# Pi_MCU_shield.net
KiCad netlist of a schematic drawn in EAGLE
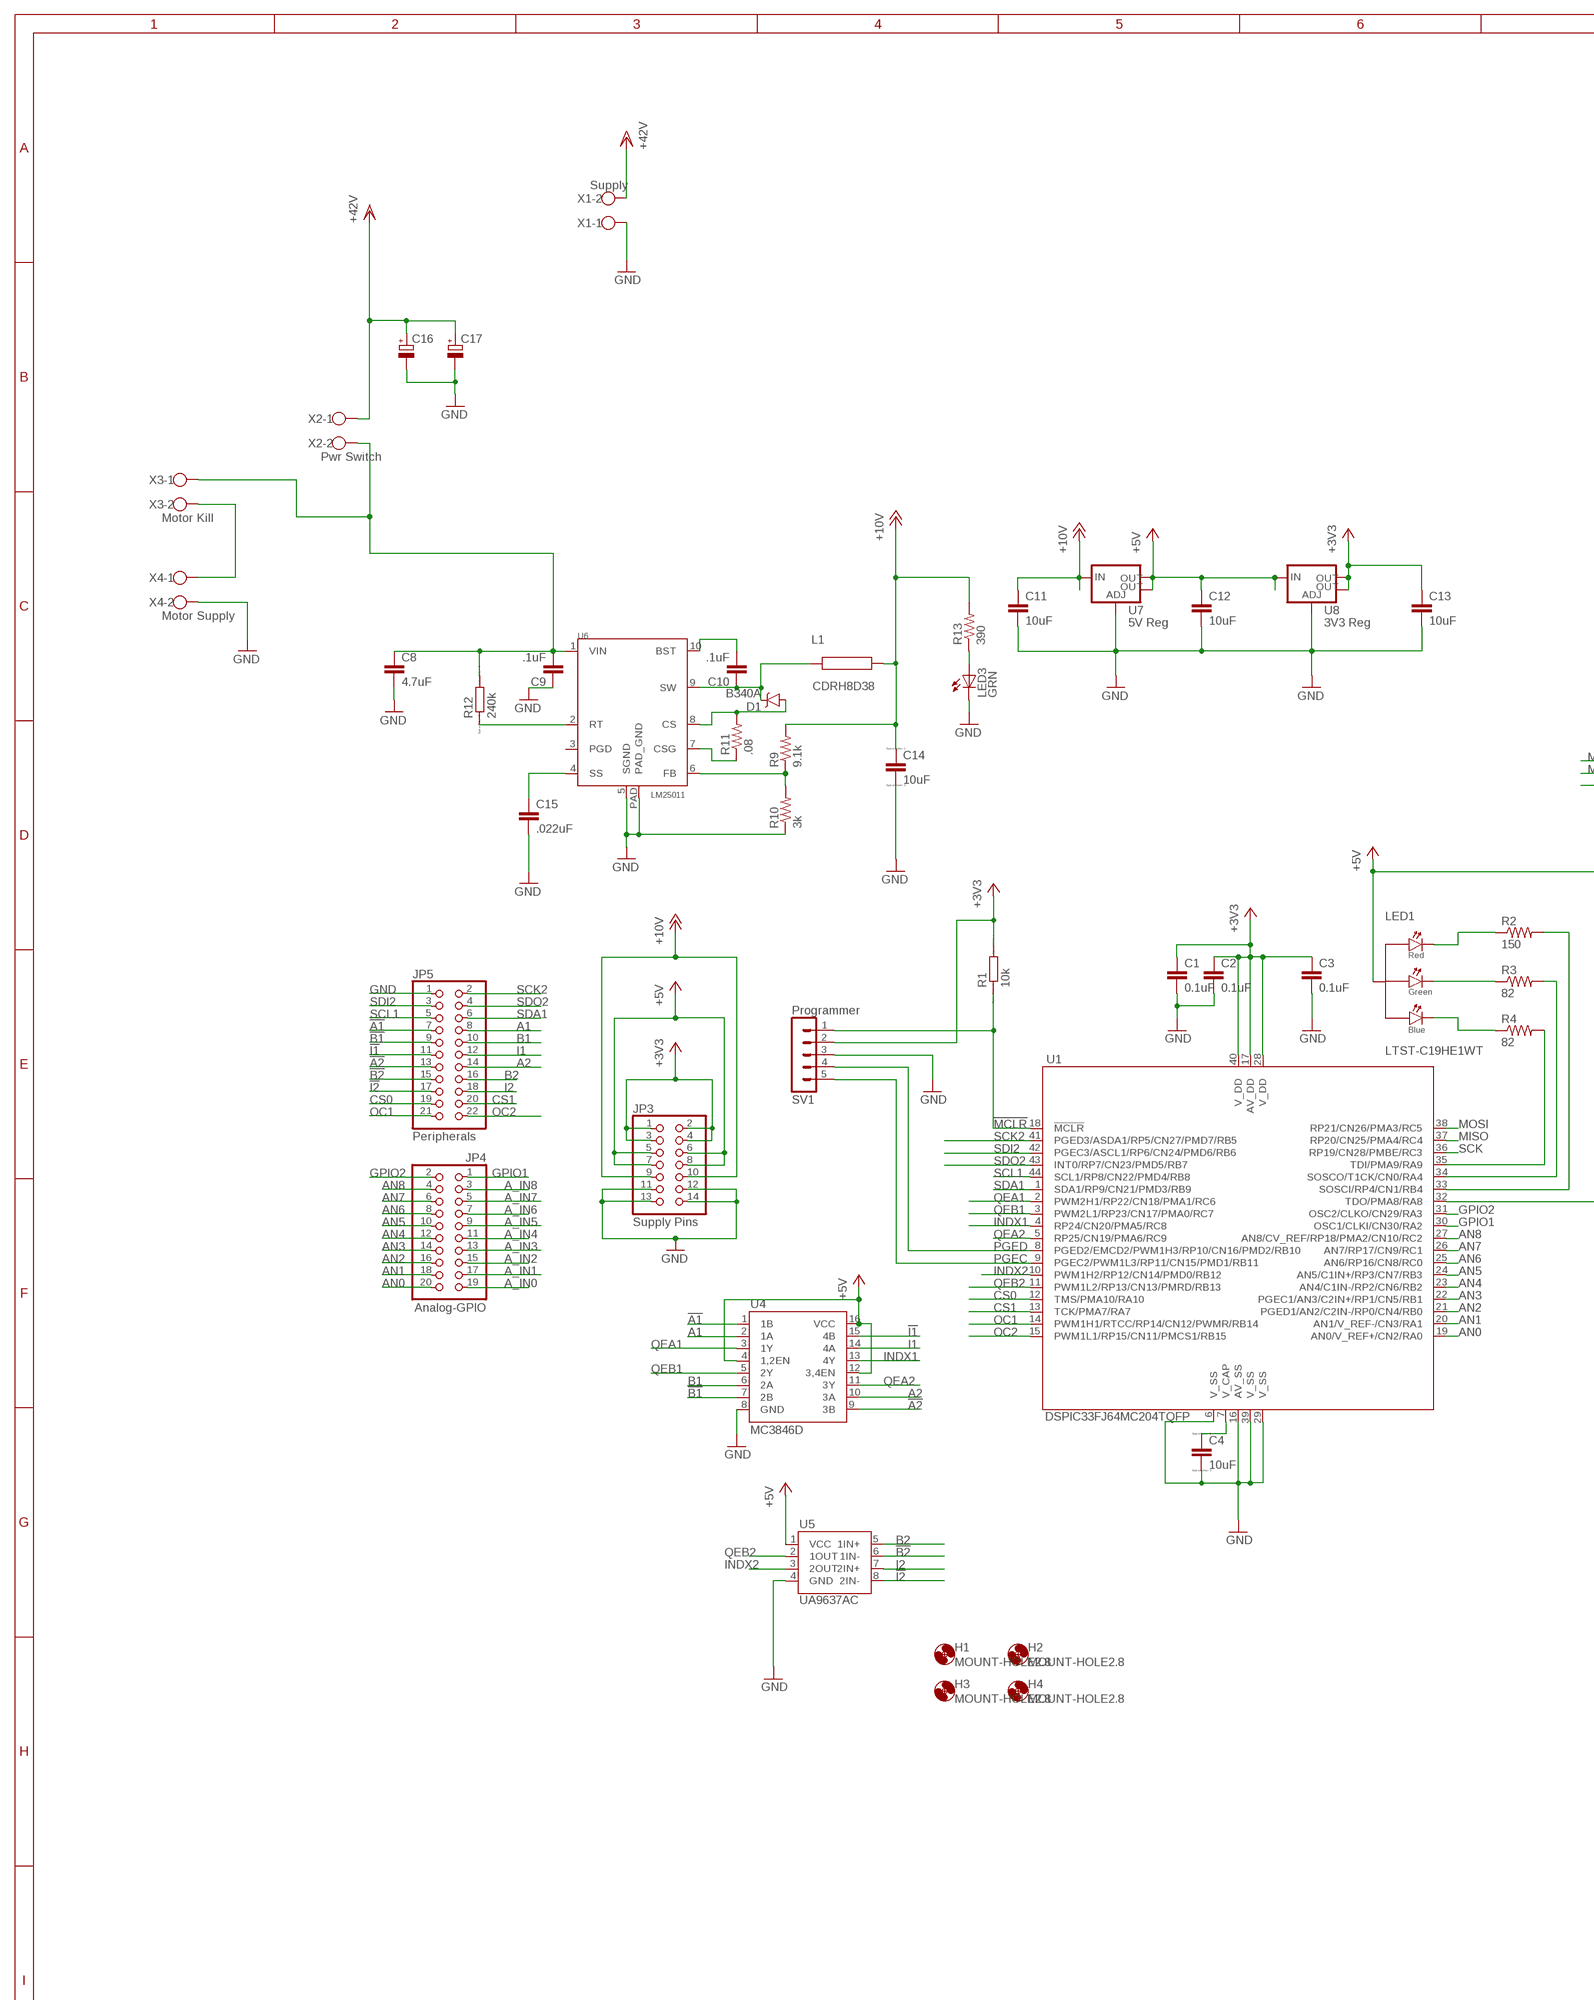
[diagram p0: schematic, sheet 1, part 1 of 2]
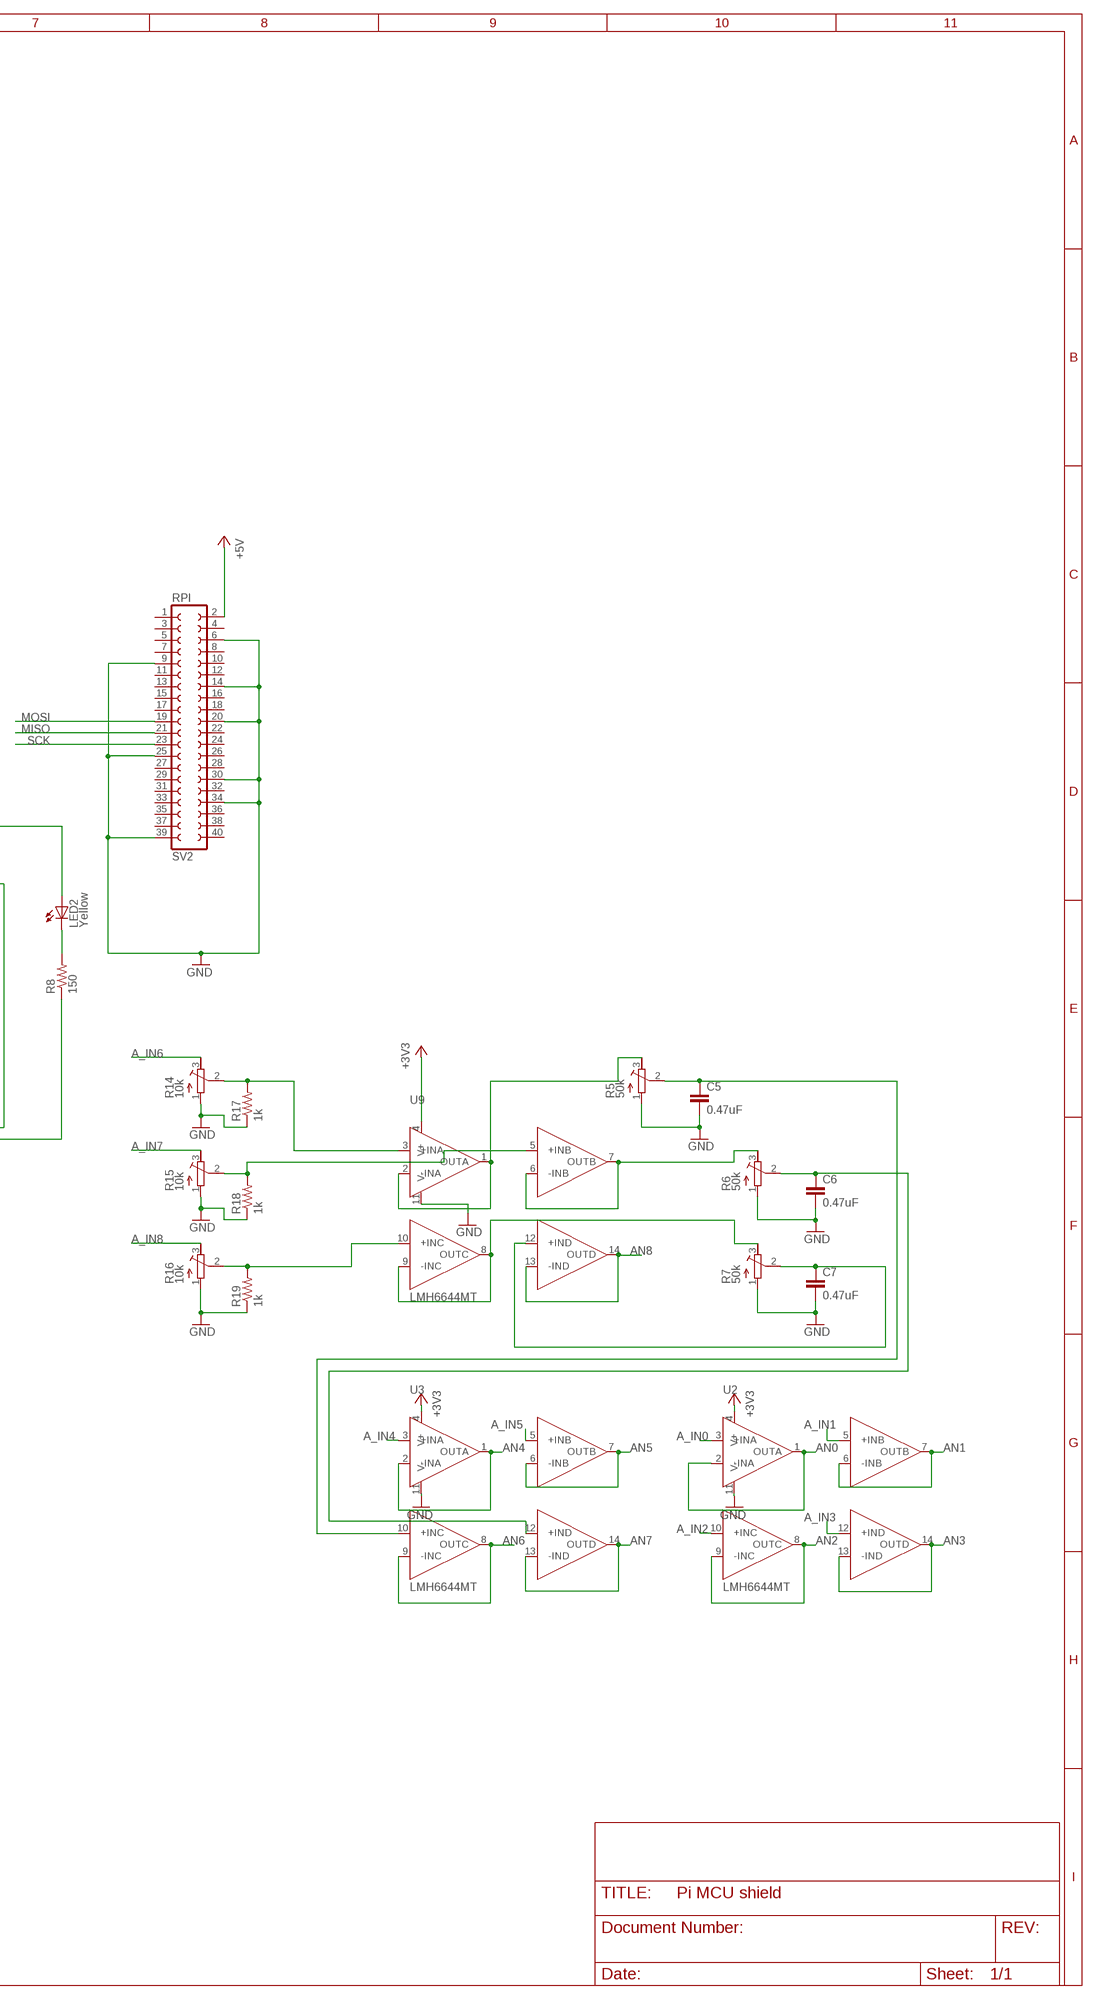
[diagram p1: schematic, sheet 1, part 2 of 2]

(export (version "E")
  (design (tool "Eeschema 10.0.6"))
  (components
    (comp (ref "C1")
      (value "0.1uF")
      (footprint "eagle-import:C0603")
      (libsource (lib "eagle-import") (part "C-EUC0603"))
    )
    (comp (ref "C2")
      (value "0.1uF")
      (footprint "eagle-import:C0603")
      (libsource (lib "eagle-import") (part "C-EUC0603"))
    )
    (comp (ref "C3")
      (value "0.1uF")
      (footprint "eagle-import:C0603")
      (libsource (lib "eagle-import") (part "C-EUC0603"))
    )
    (comp (ref "C4")
      (value "10uF")
      (footprint "eagle-import:C1206")
      (libsource (lib "eagle-import") (part "CC1206"))
    )
    (comp (ref "C5")
      (value "0.47uF")
      (footprint "eagle-import:C0603")
      (libsource (lib "eagle-import") (part "C-EUC0603"))
    )
    (comp (ref "C6")
      (value "0.47uF")
      (footprint "eagle-import:C0603")
      (libsource (lib "eagle-import") (part "C-EUC0603"))
    )
    (comp (ref "C7")
      (value "0.47uF")
      (footprint "eagle-import:C0603")
      (libsource (lib "eagle-import") (part "C-EUC0603"))
    )
    (comp (ref "C8")
      (value "4.7uF")
      (footprint "eagle-import:C1210")
      (libsource (lib "eagle-import") (part "C-EUC1210"))
    )
    (comp (ref "C9")
      (value ".1uF")
      (footprint "eagle-import:0603-CAP")
      (libsource (lib "eagle-import") (part "CAP0603-CAP"))
    )
    (comp (ref "C10")
      (value ".1uF")
      (footprint "eagle-import:0603-CAP")
      (libsource (lib "eagle-import") (part "CAP0603-CAP"))
    )
    (comp (ref "C11")
      (value "10uF")
      (footprint "eagle-import:C0805")
      (libsource (lib "eagle-import") (part "C-EUC0805"))
    )
    (comp (ref "C12")
      (value "10uF")
      (footprint "eagle-import:C0805")
      (libsource (lib "eagle-import") (part "C-EUC0805"))
    )
    (comp (ref "C13")
      (value "10uF")
      (footprint "eagle-import:C0805")
      (libsource (lib "eagle-import") (part "C-EUC0805"))
    )
    (comp (ref "C14")
      (value "10uF")
      (footprint "eagle-import:C1206")
      (libsource (lib "eagle-import") (part "CC1206"))
    )
    (comp (ref "C15")
      (value ".022uF")
      (footprint "eagle-import:0603-CAP")
      (libsource (lib "eagle-import") (part "CAP0603-CAP"))
    )
    (comp (ref "C16")
      (value "CPOL-EUE5-13")
      (footprint "eagle-import:E5-13")
      (libsource (lib "eagle-import") (part "CPOL-EUE5-13"))
    )
    (comp (ref "C17")
      (value "CPOL-EUE5-13")
      (footprint "eagle-import:E5-13")
      (libsource (lib "eagle-import") (part "CPOL-EUE5-13"))
    )
    (comp (ref "D1")
      (value "B340A")
      (footprint "eagle-import:SMA-DIODE")
      (libsource (lib "eagle-import") (part "DIODE-SCHOTTKY-B340A"))
    )
    (comp (ref "H1")
      (value "MOUNT-HOLE2.8")
      (footprint "eagle-import:2,8")
      (libsource (lib "eagle-import") (part "MOUNT-HOLE2.8"))
    )
    (comp (ref "H2")
      (value "MOUNT-HOLE2.8")
      (footprint "eagle-import:2,8")
      (libsource (lib "eagle-import") (part "MOUNT-HOLE2.8"))
    )
    (comp (ref "H3")
      (value "MOUNT-HOLE2.8")
      (footprint "eagle-import:2,8")
      (libsource (lib "eagle-import") (part "MOUNT-HOLE2.8"))
    )
    (comp (ref "H4")
      (value "MOUNT-HOLE2.8")
      (footprint "eagle-import:2,8")
      (libsource (lib "eagle-import") (part "MOUNT-HOLE2.8"))
    )
    (comp (ref "JP3")
      (value "Supply Pins")
      (footprint "eagle-import:2X07")
      (libsource (lib "eagle-import") (part "PINHD-2X7"))
    )
    (comp (ref "JP4")
      (value "Analog-GPIO")
      (footprint "eagle-import:2X10")
      (libsource (lib "eagle-import") (part "PINHD-2X10"))
    )
    (comp (ref "JP5")
      (value "Peripherals")
      (footprint "eagle-import:2X11")
      (libsource (lib "eagle-import") (part "PINHD-2X11"))
    )
    (comp (ref "L1")
      (value "CDRH8D38")
      (footprint "eagle-import:CDRH8D38")
      (libsource (lib "eagle-import") (part "CDRH8D38"))
    )
    (comp (ref "LED1")
      (value "LTST-C19HE1WT")
      (footprint "eagle-import:0606")
      (libsource (lib "eagle-import") (part "LTST-C19HE1WT"))
    )
    (comp (ref "LED2")
      (value "Yellow")
      (footprint "eagle-import:SML0603")
      (libsource (lib "eagle-import") (part "LEDSML0603"))
    )
    (comp (ref "LED3")
      (value "GRN")
      (footprint "eagle-import:CHIP-LED0805")
      (libsource (lib "eagle-import") (part "LEDCHIP-LED0805"))
    )
    (comp (ref "R1")
      (value "10k")
      (footprint "eagle-import:R0805")
      (libsource (lib "eagle-import") (part "R"))
    )
    (comp (ref "R2")
      (value "150")
      (footprint "eagle-import:R0603")
      (libsource (lib "eagle-import") (part "R-US_R0603"))
    )
    (comp (ref "R3")
      (value "82")
      (footprint "eagle-import:R0603")
      (libsource (lib "eagle-import") (part "R-US_R0603"))
    )
    (comp (ref "R4")
      (value "82")
      (footprint "eagle-import:R0603")
      (libsource (lib "eagle-import") (part "R-US_R0603"))
    )
    (comp (ref "R5")
      (value "50k")
      (footprint "eagle-import:RTRIM3224J")
      (libsource (lib "eagle-import") (part "R-TRIMM3224J"))
    )
    (comp (ref "R6")
      (value "50k")
      (footprint "eagle-import:RTRIM3224J")
      (libsource (lib "eagle-import") (part "R-TRIMM3224J"))
    )
    (comp (ref "R7")
      (value "50k")
      (footprint "eagle-import:RTRIM3224J")
      (libsource (lib "eagle-import") (part "R-TRIMM3224J"))
    )
    (comp (ref "R8")
      (value "150")
      (footprint "eagle-import:R0603")
      (libsource (lib "eagle-import") (part "R-US_R0603"))
    )
    (comp (ref "R9")
      (value "9.1k")
      (footprint "eagle-import:0603-RES")
      (libsource (lib "eagle-import") (part "RESISTOR0603-RES"))
    )
    (comp (ref "R10")
      (value "3k")
      (footprint "eagle-import:0603-RES")
      (libsource (lib "eagle-import") (part "RESISTOR0603-RES"))
    )
    (comp (ref "R11")
      (value ".08")
      (footprint "eagle-import:0603-RES")
      (libsource (lib "eagle-import") (part "RESISTOR0603-RES"))
    )
    (comp (ref "R12")
      (value "240k")
      (footprint "eagle-import:R0805")
      (libsource (lib "eagle-import") (part "R"))
    )
    (comp (ref "R13")
      (value "390")
      (footprint "eagle-import:0603-RES")
      (libsource (lib "eagle-import") (part "RESISTOR0603-RES"))
    )
    (comp (ref "R14")
      (value "10k")
      (footprint "eagle-import:RTRIM3224J")
      (libsource (lib "eagle-import") (part "R-TRIMM3224J"))
    )
    (comp (ref "R15")
      (value "10k")
      (footprint "eagle-import:RTRIM3224J")
      (libsource (lib "eagle-import") (part "R-TRIMM3224J"))
    )
    (comp (ref "R16")
      (value "10k")
      (footprint "eagle-import:RTRIM3224J")
      (libsource (lib "eagle-import") (part "R-TRIMM3224J"))
    )
    (comp (ref "R17")
      (value "1k")
      (footprint "eagle-import:R0603")
      (libsource (lib "eagle-import") (part "R-US_R0603"))
    )
    (comp (ref "R18")
      (value "1k")
      (footprint "eagle-import:R0603")
      (libsource (lib "eagle-import") (part "R-US_R0603"))
    )
    (comp (ref "R19")
      (value "1k")
      (footprint "eagle-import:R0603")
      (libsource (lib "eagle-import") (part "R-US_R0603"))
    )
    (comp (ref "SV1")
      (value "Programmer")
      (footprint "eagle-import:MA05-1")
      (libsource (lib "eagle-import") (part "MA05-1"))
    )
    (comp (ref "SV2")
      (value "RPI")
      (footprint "eagle-import:FE20-2")
      (libsource (lib "eagle-import") (part "FE20-2"))
    )
    (comp (ref "U1")
      (value "DSPIC33FJ64MC204TQFP")
      (footprint "eagle-import:TQFP44")
      (libsource (lib "eagle-import") (part "DSPIC33FJ64MC204TQFP"))
    )
    (comp (ref "U2")
      (value "LMH6644MT")
      (footprint "eagle-import:TSSOP14")
      (libsource (lib "eagle-import") (part "LMH6644MT"))
    )
    (comp (ref "U3")
      (value "LMH6644MT")
      (footprint "eagle-import:TSSOP14")
      (libsource (lib "eagle-import") (part "LMH6644MT"))
    )
    (comp (ref "U4")
      (value "MC3846D")
      (footprint "eagle-import:SO-16")
      (libsource (lib "eagle-import") (part "MC3846D"))
    )
    (comp (ref "U5")
      (value "UA9637AC")
      (footprint "eagle-import:SO-08")
      (libsource (lib "eagle-import") (part "UA9637AC"))
    )
    (comp (ref "U6")
      (value "LM25011")
      (footprint "eagle-import:HVSS0P-10")
      (libsource (lib "eagle-import") (part "LM25011"))
    )
    (comp (ref "U7")
      (value "5V Reg")
      (footprint "eagle-import:SOT223")
      (libsource (lib "eagle-import") (part "V_REG_LM1117SOT223"))
    )
    (comp (ref "U8")
      (value "3V3 Reg")
      (footprint "eagle-import:SOT223")
      (libsource (lib "eagle-import") (part "V_REG_LM1117SOT223"))
    )
    (comp (ref "U9")
      (value "LMH6644MT")
      (footprint "eagle-import:TSSOP14")
      (libsource (lib "eagle-import") (part "LMH6644MT"))
    )
    (comp (ref "X1")
      (value "Supply")
      (footprint "eagle-import:W237-102")
      (fields (field (name "MPN") "237-102"))
      (libsource (lib "eagle-import") (part "W237-102"))
    )
    (comp (ref "X2")
      (value "Pwr Switch")
      (footprint "eagle-import:W237-102")
      (fields (field (name "MPN") "237-102"))
      (libsource (lib "eagle-import") (part "W237-102"))
    )
    (comp (ref "X3")
      (value "Motor Kill")
      (footprint "eagle-import:W237-102")
      (fields (field (name "MPN") "237-102"))
      (libsource (lib "eagle-import") (part "W237-102"))
    )
    (comp (ref "X4")
      (value "Motor Supply")
      (footprint "eagle-import:W237-102")
      (fields (field (name "MPN") "237-102"))
      (libsource (lib "eagle-import") (part "W237-102"))
    )
  )
  (nets
    (net (code "1") (name "+3V3") (class "Default")
      (node (ref "C1") (pin "1") (pinfunction "1_1") (pintype "passive"))
      (node (ref "C13") (pin "1") (pinfunction "1_1") (pintype "passive"))
      (node (ref "C2") (pin "1") (pinfunction "1_1") (pintype "passive"))
      (node (ref "C3") (pin "1") (pinfunction "1_1") (pintype "passive"))
      (node (ref "JP3") (pin "1") (pinfunction "1_1") (pintype "passive"))
      (node (ref "JP3") (pin "2") (pinfunction "2_2") (pintype "passive"))
      (node (ref "JP3") (pin "3") (pinfunction "3_3") (pintype "passive"))
      (node (ref "JP3") (pin "4") (pinfunction "4_4") (pintype "passive"))
      (node (ref "R1") (pin "2") (pinfunction "2_2") (pintype "passive"))
      (node (ref "SV1") (pin "2") (pinfunction "2_2") (pintype "passive"))
      (node (ref "U1") (pin "17") (pinfunction "AV_DD_17") (pintype "power_in"))
      (node (ref "U1") (pin "28") (pinfunction "V_DD_28") (pintype "power_in"))
      (node (ref "U1") (pin "40") (pinfunction "V_DD_40") (pintype "power_in"))
      (node (ref "U2") (pin "4") (pinfunction "V+_4") (pintype "bidirectional"))
      (node (ref "U3") (pin "4") (pinfunction "V+_4") (pintype "bidirectional"))
      (node (ref "U8") (pin "2") (pinfunction "OUT_2") (pintype "output"))
      (node (ref "U8") (pin "4") (pinfunction "OUT_4") (pintype "output"))
      (node (ref "U9") (pin "4") (pinfunction "V+_4") (pintype "bidirectional"))
    )
    (net (code "2") (name "+5V") (class "Default")
      (node (ref "C12") (pin "1") (pinfunction "1_1") (pintype "passive"))
      (node (ref "JP3") (pin "5") (pinfunction "5_5") (pintype "passive"))
      (node (ref "JP3") (pin "6") (pinfunction "6_6") (pintype "passive"))
      (node (ref "JP3") (pin "7") (pinfunction "7_7") (pintype "passive"))
      (node (ref "JP3") (pin "8") (pinfunction "8_8") (pintype "passive"))
      (node (ref "LED1") (pin "4") (pinfunction "ANODE_4") (pintype "passive"))
      (node (ref "LED2") (pin "A") (pinfunction "A_A") (pintype "passive"))
      (node (ref "SV2") (pin "2") (pinfunction "2_2") (pintype "passive"))
      (node (ref "U4") (pin "12") (pinfunction "3,4EN_12") (pintype "bidirectional"))
      (node (ref "U4") (pin "16") (pinfunction "VCC_16") (pintype "power_in"))
      (node (ref "U4") (pin "4") (pinfunction "1,2EN_4") (pintype "input"))
      (node (ref "U5") (pin "1") (pinfunction "VCC_1") (pintype "power_in"))
      (node (ref "U7") (pin "2") (pinfunction "OUT_2") (pintype "output"))
      (node (ref "U7") (pin "4") (pinfunction "OUT_4") (pintype "output"))
      (node (ref "U8") (pin "3") (pinfunction "IN_3") (pintype "input"))
    )
    (net (code "3") (name "+10V") (class "Default")
      (node (ref "C11") (pin "1") (pinfunction "1_1") (pintype "passive"))
      (node (ref "C14") (pin "1") (pinfunction "1_1") (pintype "passive"))
      (node (ref "JP3") (pin "10") (pinfunction "10_10") (pintype "passive"))
      (node (ref "JP3") (pin "9") (pinfunction "9_9") (pintype "passive"))
      (node (ref "L1") (pin "P$2") (pinfunction "2_P$2") (pintype "passive"))
      (node (ref "R13") (pin "2") (pinfunction "2_2") (pintype "passive"))
      (node (ref "R9") (pin "2") (pinfunction "2_2") (pintype "passive"))
      (node (ref "U7") (pin "3") (pinfunction "IN_3") (pintype "input"))
    )
    (net (code "4") (name "+42V") (class "Default")
      (node (ref "C16") (pin "+") (pinfunction "+_+") (pintype "passive"))
      (node (ref "C17") (pin "+") (pinfunction "+_+") (pintype "passive"))
      (node (ref "X1") (pin "2") (pinfunction "KL_2") (pintype "passive"))
      (node (ref "X2") (pin "1") (pinfunction "KL_1") (pintype "passive"))
    )
    (net (code "5") (name "/A1") (class "Default")
      (node (ref "JP5") (pin "8") (pinfunction "8_8") (pintype "passive"))
      (node (ref "U4") (pin "2") (pinfunction "1A_2") (pintype "input"))
    )
    (net (code "6") (name "/A2") (class "Default")
      (node (ref "JP5") (pin "14") (pinfunction "14_14") (pintype "passive"))
      (node (ref "U4") (pin "10") (pinfunction "3A_10") (pintype "input"))
    )
    (net (code "7") (name "/AN0") (class "Default")
      (node (ref "JP4") (pin "20") (pinfunction "20_20") (pintype "passive"))
      (node (ref "U1") (pin "19") (pinfunction "AN0/V_REF+/CN2/RA0_19") (pintype "bidirectional"))
      (node (ref "U2") (pin "1") (pinfunction "OUTA_1") (pintype "bidirectional"))
      (node (ref "U2") (pin "2") (pinfunction "-INA_2") (pintype "bidirectional"))
    )
    (net (code "8") (name "/AN1") (class "Default")
      (node (ref "JP4") (pin "18") (pinfunction "18_18") (pintype "passive"))
      (node (ref "U1") (pin "20") (pinfunction "AN1/V_REF-/CN3/RA1_20") (pintype "bidirectional"))
      (node (ref "U2") (pin "6") (pinfunction "-INB_6") (pintype "bidirectional"))
      (node (ref "U2") (pin "7") (pinfunction "OUTB_7") (pintype "bidirectional"))
    )
    (net (code "9") (name "/AN2") (class "Default")
      (node (ref "JP4") (pin "16") (pinfunction "16_16") (pintype "passive"))
      (node (ref "U1") (pin "21") (pinfunction "PGED1/AN2/C2IN-/RP0/CN4/RB0_21") (pintype "bidirectional"))
      (node (ref "U2") (pin "8") (pinfunction "OUTC_8") (pintype "bidirectional"))
      (node (ref "U2") (pin "9") (pinfunction "-INC_9") (pintype "bidirectional"))
    )
    (net (code "10") (name "/AN3") (class "Default")
      (node (ref "JP4") (pin "14") (pinfunction "14_14") (pintype "passive"))
      (node (ref "U1") (pin "22") (pinfunction "PGEC1/AN3/C2IN+/RP1/CN5/RB1_22") (pintype "bidirectional"))
      (node (ref "U2") (pin "13") (pinfunction "-IND_13") (pintype "bidirectional"))
      (node (ref "U2") (pin "14") (pinfunction "OUTD_14") (pintype "bidirectional"))
    )
    (net (code "11") (name "/AN4") (class "Default")
      (node (ref "JP4") (pin "12") (pinfunction "12_12") (pintype "passive"))
      (node (ref "U1") (pin "23") (pinfunction "AN4/C1IN-/RP2/CN6/RB2_23") (pintype "bidirectional"))
      (node (ref "U3") (pin "1") (pinfunction "OUTA_1") (pintype "bidirectional"))
      (node (ref "U3") (pin "2") (pinfunction "-INA_2") (pintype "bidirectional"))
    )
    (net (code "12") (name "/AN5") (class "Default")
      (node (ref "JP4") (pin "10") (pinfunction "10_10") (pintype "passive"))
      (node (ref "U1") (pin "24") (pinfunction "AN5/C1IN+/RP3/CN7/RB3_24") (pintype "bidirectional"))
      (node (ref "U3") (pin "6") (pinfunction "-INB_6") (pintype "bidirectional"))
      (node (ref "U3") (pin "7") (pinfunction "OUTB_7") (pintype "bidirectional"))
    )
    (net (code "13") (name "/AN6") (class "Default")
      (node (ref "JP4") (pin "8") (pinfunction "8_8") (pintype "passive"))
      (node (ref "U1") (pin "25") (pinfunction "AN6/RP16/CN8/RC0_25") (pintype "bidirectional"))
      (node (ref "U3") (pin "8") (pinfunction "OUTC_8") (pintype "bidirectional"))
      (node (ref "U3") (pin "9") (pinfunction "-INC_9") (pintype "bidirectional"))
    )
    (net (code "14") (name "/AN7") (class "Default")
      (node (ref "JP4") (pin "6") (pinfunction "6_6") (pintype "passive"))
      (node (ref "U1") (pin "26") (pinfunction "AN7/RP17/CN9/RC1_26") (pintype "bidirectional"))
      (node (ref "U3") (pin "13") (pinfunction "-IND_13") (pintype "bidirectional"))
      (node (ref "U3") (pin "14") (pinfunction "OUTD_14") (pintype "bidirectional"))
    )
    (net (code "15") (name "/AN8") (class "Default")
      (node (ref "JP4") (pin "4") (pinfunction "4_4") (pintype "passive"))
      (node (ref "U1") (pin "27") (pinfunction "AN8/CV_REF/RP18/PMA2/CN10/RC2_27") (pintype "bidirectional"))
      (node (ref "U9") (pin "13") (pinfunction "-IND_13") (pintype "bidirectional"))
      (node (ref "U9") (pin "14") (pinfunction "OUTD_14") (pintype "bidirectional"))
    )
    (net (code "16") (name "/A_IN0") (class "Default")
      (node (ref "JP4") (pin "19") (pinfunction "19_19") (pintype "passive"))
      (node (ref "U2") (pin "3") (pinfunction "+INA_3") (pintype "bidirectional"))
    )
    (net (code "17") (name "/A_IN1") (class "Default")
      (node (ref "JP4") (pin "17") (pinfunction "17_17") (pintype "passive"))
      (node (ref "U2") (pin "5") (pinfunction "+INB_5") (pintype "bidirectional"))
    )
    (net (code "18") (name "/A_IN2") (class "Default")
      (node (ref "JP4") (pin "15") (pinfunction "15_15") (pintype "passive"))
      (node (ref "U2") (pin "10") (pinfunction "+INC_10") (pintype "bidirectional"))
    )
    (net (code "19") (name "/A_IN3") (class "Default")
      (node (ref "JP4") (pin "13") (pinfunction "13_13") (pintype "passive"))
      (node (ref "U2") (pin "12") (pinfunction "+IND_12") (pintype "bidirectional"))
    )
    (net (code "20") (name "/A_IN4") (class "Default")
      (node (ref "JP4") (pin "11") (pinfunction "11_11") (pintype "passive"))
      (node (ref "U3") (pin "3") (pinfunction "+INA_3") (pintype "bidirectional"))
    )
    (net (code "21") (name "/A_IN5") (class "Default")
      (node (ref "JP4") (pin "9") (pinfunction "9_9") (pintype "passive"))
      (node (ref "U3") (pin "5") (pinfunction "+INB_5") (pintype "bidirectional"))
    )
    (net (code "22") (name "/A_IN6") (class "Default")
      (node (ref "JP4") (pin "7") (pinfunction "7_7") (pintype "passive"))
      (node (ref "R14") (pin "3") (pinfunction "E_3") (pintype "passive"))
    )
    (net (code "23") (name "/A_IN7") (class "Default")
      (node (ref "JP4") (pin "5") (pinfunction "5_5") (pintype "passive"))
      (node (ref "R15") (pin "3") (pinfunction "E_3") (pintype "passive"))
    )
    (net (code "24") (name "/A_IN8") (class "Default")
      (node (ref "JP4") (pin "3") (pinfunction "3_3") (pintype "passive"))
      (node (ref "R16") (pin "3") (pinfunction "E_3") (pintype "passive"))
    )
    (net (code "25") (name "/B1") (class "Default")
      (node (ref "JP5") (pin "10") (pinfunction "10_10") (pintype "passive"))
      (node (ref "U4") (pin "6") (pinfunction "2A_6") (pintype "input"))
    )
    (net (code "26") (name "/B2") (class "Default")
      (node (ref "JP5") (pin "16") (pinfunction "16_16") (pintype "passive"))
      (node (ref "U5") (pin "5") (pinfunction "1IN+_5") (pintype "input"))
    )
    (net (code "27") (name "/CS0") (class "Default")
      (node (ref "JP5") (pin "19") (pinfunction "19_19") (pintype "passive"))
      (node (ref "U1") (pin "12") (pinfunction "TMS/PMA10/RA10_12") (pintype "bidirectional"))
    )
    (net (code "28") (name "/CS1") (class "Default")
      (node (ref "JP5") (pin "20") (pinfunction "20_20") (pintype "passive"))
      (node (ref "U1") (pin "13") (pinfunction "TCK/PMA7/RA7_13") (pintype "bidirectional"))
    )
    (net (code "29") (name "/GPIO1") (class "Default")
      (node (ref "JP4") (pin "1") (pinfunction "1_1") (pintype "passive"))
      (node (ref "U1") (pin "30") (pinfunction "OSC1/CLKI/CN30/RA2_30") (pintype "bidirectional"))
    )
    (net (code "30") (name "/GPIO2") (class "Default")
      (node (ref "JP4") (pin "2") (pinfunction "2_2") (pintype "passive"))
      (node (ref "U1") (pin "31") (pinfunction "OSC2/CLKO/CN29/RA3_31") (pintype "bidirectional"))
    )
    (net (code "31") (name "/I1") (class "Default")
      (node (ref "JP5") (pin "12") (pinfunction "12_12") (pintype "passive"))
      (node (ref "U4") (pin "14") (pinfunction "4A_14") (pintype "input"))
    )
    (net (code "32") (name "/I2") (class "Default")
      (node (ref "JP5") (pin "18") (pinfunction "18_18") (pintype "passive"))
      (node (ref "U5") (pin "7") (pinfunction "2IN+_7") (pintype "input"))
    )
    (net (code "33") (name "/INDX1") (class "Default")
      (node (ref "U1") (pin "4") (pinfunction "RP24/CN20/PMA5/RC8_4") (pintype "bidirectional"))
      (node (ref "U4") (pin "13") (pinfunction "4Y_13") (pintype "output"))
    )
    (net (code "34") (name "/INDX2") (class "Default")
      (node (ref "U1") (pin "10") (pinfunction "PWM1H2/RP12/CN14/PMD0/RB12_10") (pintype "bidirectional"))
      (node (ref "U5") (pin "3") (pinfunction "2OUT_3") (pintype "output"))
    )
    (net (code "35") (name "/MISO") (class "Default")
      (node (ref "SV2") (pin "21") (pinfunction "21_21") (pintype "passive"))
      (node (ref "U1") (pin "37") (pinfunction "RP20/CN25/PMA4/RC4_37") (pintype "bidirectional"))
    )
    (net (code "36") (name "/MOSI") (class "Default")
      (node (ref "SV2") (pin "19") (pinfunction "19_19") (pintype "passive"))
      (node (ref "U1") (pin "38") (pinfunction "RP21/CN26/PMA3/RC5_38") (pintype "bidirectional"))
    )
    (net (code "37") (name "/OC1") (class "Default")
      (node (ref "JP5") (pin "21") (pinfunction "21_21") (pintype "passive"))
      (node (ref "U1") (pin "14") (pinfunction "PWM1H1/RTCC/RP14/CN12/PWMR/RB14_14") (pintype "bidirectional"))
    )
    (net (code "38") (name "/OC2") (class "Default")
      (node (ref "JP5") (pin "22") (pinfunction "22_22") (pintype "passive"))
      (node (ref "U1") (pin "15") (pinfunction "PWM1L1/RP15/CN11/PMCS1/RB15_15") (pintype "bidirectional"))
    )
    (net (code "39") (name "/PGEC") (class "Default")
      (node (ref "SV1") (pin "5") (pinfunction "5_5") (pintype "passive"))
      (node (ref "U1") (pin "9") (pinfunction "PGEC2/PWM1L3/RP11/CN15/PMD1/RB11_9") (pintype "bidirectional"))
    )
    (net (code "40") (name "/PGED") (class "Default")
      (node (ref "SV1") (pin "4") (pinfunction "4_4") (pintype "passive"))
      (node (ref "U1") (pin "8") (pinfunction "PGED2/EMCD2/PWM1H3/RP10/CN16/PMD2/RB10_8") (pintype "bidirectional"))
    )
    (net (code "41") (name "/QEA1") (class "Default")
      (node (ref "U1") (pin "2") (pinfunction "PWM2H1/RP22/CN18/PMA1/RC6_2") (pintype "bidirectional"))
      (node (ref "U4") (pin "3") (pinfunction "1Y_3") (pintype "output"))
    )
    (net (code "42") (name "/QEA2") (class "Default")
      (node (ref "U1") (pin "5") (pinfunction "RP25/CN19/PMA6/RC9_5") (pintype "bidirectional"))
      (node (ref "U4") (pin "11") (pinfunction "3Y_11") (pintype "output"))
    )
    (net (code "43") (name "/QEB1") (class "Default")
      (node (ref "U1") (pin "3") (pinfunction "PWM2L1/RP23/CN17/PMA0/RC7_3") (pintype "bidirectional"))
      (node (ref "U4") (pin "5") (pinfunction "2Y_5") (pintype "output"))
    )
    (net (code "44") (name "/QEB2") (class "Default")
      (node (ref "U1") (pin "11") (pinfunction "PWM1L2/RP13/CN13/PMRD/RB13_11") (pintype "bidirectional"))
      (node (ref "U5") (pin "2") (pinfunction "1OUT_2") (pintype "output"))
    )
    (net (code "45") (name "/SCK") (class "Default")
      (node (ref "SV2") (pin "23") (pinfunction "23_23") (pintype "passive"))
      (node (ref "U1") (pin "36") (pinfunction "RP19/CN28/PMBE/RC3_36") (pintype "bidirectional"))
    )
    (net (code "46") (name "/SCK2") (class "Default")
      (node (ref "JP5") (pin "2") (pinfunction "2_2") (pintype "passive"))
      (node (ref "U1") (pin "41") (pinfunction "PGED3/ASDA1/RP5/CN27/PMD7/RB5_41") (pintype "bidirectional"))
    )
    (net (code "47") (name "/SCL1") (class "Default")
      (node (ref "JP5") (pin "5") (pinfunction "5_5") (pintype "passive"))
      (node (ref "U1") (pin "44") (pinfunction "SCL1/RP8/CN22/PMD4/RB8_44") (pintype "bidirectional"))
    )
    (net (code "48") (name "/SDA1") (class "Default")
      (node (ref "JP5") (pin "6") (pinfunction "6_6") (pintype "passive"))
      (node (ref "U1") (pin "1") (pinfunction "SDA1/RP9/CN21/PMD3/RB9_1") (pintype "bidirectional"))
    )
    (net (code "49") (name "/SDI2") (class "Default")
      (node (ref "JP5") (pin "3") (pinfunction "3_3") (pintype "passive"))
      (node (ref "U1") (pin "42") (pinfunction "PGEC3/ASCL1/RP6/CN24/PMD6/RB6_42") (pintype "bidirectional"))
    )
    (net (code "50") (name "/SDO2") (class "Default")
      (node (ref "JP5") (pin "4") (pinfunction "4_4") (pintype "passive"))
      (node (ref "U1") (pin "43") (pinfunction "INT0/RP7/CN23/PMD5/RB7_43") (pintype "bidirectional"))
    )
    (net (code "51") (name "/~{A1}") (class "Default")
      (node (ref "JP5") (pin "7") (pinfunction "7_7") (pintype "passive"))
      (node (ref "U4") (pin "1") (pinfunction "1B_1") (pintype "input"))
    )
    (net (code "52") (name "/~{A2}") (class "Default")
      (node (ref "JP5") (pin "13") (pinfunction "13_13") (pintype "passive"))
      (node (ref "U4") (pin "9") (pinfunction "3B_9") (pintype "input"))
    )
    (net (code "53") (name "/~{B1}") (class "Default")
      (node (ref "JP5") (pin "9") (pinfunction "9_9") (pintype "passive"))
      (node (ref "U4") (pin "7") (pinfunction "2B_7") (pintype "input"))
    )
    (net (code "54") (name "/~{B2}") (class "Default")
      (node (ref "JP5") (pin "15") (pinfunction "15_15") (pintype "passive"))
      (node (ref "U5") (pin "6") (pinfunction "1IN-_6") (pintype "input"))
    )
    (net (code "55") (name "/~{I1}") (class "Default")
      (node (ref "JP5") (pin "11") (pinfunction "11_11") (pintype "passive"))
      (node (ref "U4") (pin "15") (pinfunction "4B_15") (pintype "input"))
    )
    (net (code "56") (name "/~{I2}") (class "Default")
      (node (ref "JP5") (pin "17") (pinfunction "17_17") (pintype "passive"))
      (node (ref "U5") (pin "8") (pinfunction "2IN-_8") (pintype "input"))
    )
    (net (code "57") (name "/~{MCLR}") (class "Default")
      (node (ref "R1") (pin "1") (pinfunction "1_1") (pintype "passive"))
      (node (ref "SV1") (pin "1") (pinfunction "1_1") (pintype "passive"))
      (node (ref "U1") (pin "18") (pinfunction "~{MCLR}_18") (pintype "bidirectional"))
    )
    (net (code "58") (name "GND") (class "Default")
      (node (ref "C1") (pin "2") (pinfunction "2_2") (pintype "passive"))
      (node (ref "C11") (pin "2") (pinfunction "2_2") (pintype "passive"))
      (node (ref "C12") (pin "2") (pinfunction "2_2") (pintype "passive"))
      (node (ref "C13") (pin "2") (pinfunction "2_2") (pintype "passive"))
      (node (ref "C14") (pin "2") (pinfunction "2_2") (pintype "passive"))
      (node (ref "C15") (pin "2") (pinfunction "2_2") (pintype "passive"))
      (node (ref "C16") (pin "-") (pinfunction "-_-") (pintype "passive"))
      (node (ref "C17") (pin "-") (pinfunction "-_-") (pintype "passive"))
      (node (ref "C2") (pin "2") (pinfunction "2_2") (pintype "passive"))
      (node (ref "C3") (pin "2") (pinfunction "2_2") (pintype "passive"))
      (node (ref "C4") (pin "2") (pinfunction "2_2") (pintype "passive"))
      (node (ref "C5") (pin "2") (pinfunction "2_2") (pintype "passive"))
      (node (ref "C6") (pin "2") (pinfunction "2_2") (pintype "passive"))
      (node (ref "C7") (pin "2") (pinfunction "2_2") (pintype "passive"))
      (node (ref "C8") (pin "2") (pinfunction "2_2") (pintype "passive"))
      (node (ref "C9") (pin "1") (pinfunction "1_1") (pintype "passive"))
      (node (ref "JP3") (pin "11") (pinfunction "11_11") (pintype "passive"))
      (node (ref "JP3") (pin "12") (pinfunction "12_12") (pintype "passive"))
      (node (ref "JP3") (pin "13") (pinfunction "13_13") (pintype "passive"))
      (node (ref "JP3") (pin "14") (pinfunction "14_14") (pintype "passive"))
      (node (ref "JP5") (pin "1") (pinfunction "1_1") (pintype "passive"))
      (node (ref "LED3") (pin "C") (pinfunction "C_C") (pintype "passive"))
      (node (ref "R10") (pin "1") (pinfunction "1_1") (pintype "passive"))
      (node (ref "R14") (pin "1") (pinfunction "A_1") (pintype "passive"))
      (node (ref "R15") (pin "1") (pinfunction "A_1") (pintype "passive"))
      (node (ref "R16") (pin "1") (pinfunction "A_1") (pintype "passive"))
      (node (ref "R17") (pin "1") (pinfunction "1_1") (pintype "passive"))
      (node (ref "R18") (pin "1") (pinfunction "1_1") (pintype "passive"))
      (node (ref "R19") (pin "1") (pinfunction "1_1") (pintype "passive"))
      (node (ref "R5") (pin "1") (pinfunction "A_1") (pintype "passive"))
      (node (ref "R6") (pin "1") (pinfunction "A_1") (pintype "passive"))
      (node (ref "R7") (pin "1") (pinfunction "A_1") (pintype "passive"))
      (node (ref "SV1") (pin "3") (pinfunction "3_3") (pintype "passive"))
      (node (ref "SV2") (pin "14") (pinfunction "14_14") (pintype "passive"))
      (node (ref "SV2") (pin "20") (pinfunction "20_20") (pintype "passive"))
      (node (ref "SV2") (pin "25") (pinfunction "25_25") (pintype "passive"))
      (node (ref "SV2") (pin "30") (pinfunction "30_30") (pintype "passive"))
      (node (ref "SV2") (pin "34") (pinfunction "34_34") (pintype "passive"))
      (node (ref "SV2") (pin "39") (pinfunction "39_39") (pintype "passive"))
      (node (ref "SV2") (pin "6") (pinfunction "6_6") (pintype "passive"))
      (node (ref "SV2") (pin "9") (pinfunction "9_9") (pintype "passive"))
      (node (ref "U1") (pin "16") (pinfunction "AV_SS_16") (pintype "power_in"))
      (node (ref "U1") (pin "29") (pinfunction "V_SS_29") (pintype "power_in"))
      (node (ref "U1") (pin "39") (pinfunction "V_SS_39") (pintype "power_in"))
      (node (ref "U1") (pin "6") (pinfunction "V_SS_6") (pintype "power_in"))
      (node (ref "U2") (pin "11") (pinfunction "V-_11") (pintype "bidirectional"))
      (node (ref "U3") (pin "11") (pinfunction "V-_11") (pintype "bidirectional"))
      (node (ref "U4") (pin "8") (pinfunction "GND_8") (pintype "power_in"))
      (node (ref "U5") (pin "4") (pinfunction "GND_4") (pintype "power_in"))
      (node (ref "U6") (pin "5") (pinfunction "SGND_5") (pintype "bidirectional"))
      (node (ref "U6") (pin "PAD") (pinfunction "PAD_GND_PAD") (pintype "bidirectional"))
      (node (ref "U7") (pin "1") (pinfunction "ADJ_1") (pintype "input"))
      (node (ref "U8") (pin "1") (pinfunction "ADJ_1") (pintype "input"))
      (node (ref "U9") (pin "11") (pinfunction "V-_11") (pintype "bidirectional"))
      (node (ref "X1") (pin "1") (pinfunction "KL_1") (pintype "passive"))
      (node (ref "X4") (pin "2") (pinfunction "KL_2") (pintype "passive"))
    )
    (net (code "59") (name "Net-(L1-1)") (class "Default")
      (node (ref "C10") (pin "1") (pinfunction "1_1") (pintype "passive"))
      (node (ref "D1") (pin "C") (pinfunction "C_C") (pintype "passive"))
      (node (ref "L1") (pin "P$1") (pinfunction "1_P$1") (pintype "passive"))
      (node (ref "U6") (pin "9") (pinfunction "SW_9") (pintype "bidirectional"))
    )
    (net (code "60") (name "Net-(LED1-B_CATHODE)") (class "Default")
      (node (ref "LED1") (pin "3") (pinfunction "B_CATHODE_3") (pintype "passive"))
      (node (ref "R4") (pin "1") (pinfunction "1_1") (pintype "passive"))
    )
    (net (code "61") (name "Net-(LED1-G_CATHODE)") (class "Default")
      (node (ref "LED1") (pin "2") (pinfunction "G_CATHODE_2") (pintype "passive"))
      (node (ref "R3") (pin "1") (pinfunction "1_1") (pintype "passive"))
    )
    (net (code "62") (name "Net-(LED1-R_CATHODE)") (class "Default")
      (node (ref "LED1") (pin "1") (pinfunction "R_CATHODE_1") (pintype "passive"))
      (node (ref "R2") (pin "1") (pinfunction "1_1") (pintype "passive"))
    )
    (net (code "63") (name "Net-(LED2-PadC)") (class "Default")
      (node (ref "LED2") (pin "C") (pinfunction "C_C") (pintype "passive"))
      (node (ref "R8") (pin "2") (pinfunction "2_2") (pintype "passive"))
    )
    (net (code "64") (name "Net-(LED3-PadA)") (class "Default")
      (node (ref "LED3") (pin "A") (pinfunction "A_A") (pintype "passive"))
      (node (ref "R13") (pin "1") (pinfunction "1_1") (pintype "passive"))
    )
    (net (code "65") (name "Net-(R5-E)") (class "Default")
      (node (ref "R5") (pin "3") (pinfunction "E_3") (pintype "passive"))
      (node (ref "U9") (pin "1") (pinfunction "OUTA_1") (pintype "bidirectional"))
      (node (ref "U9") (pin "2") (pinfunction "-INA_2") (pintype "bidirectional"))
    )
    (net (code "66") (name "Net-(R5-S)") (class "Default")
      (node (ref "C5") (pin "1") (pinfunction "1_1") (pintype "passive"))
      (node (ref "R5") (pin "2") (pinfunction "S_2") (pintype "passive"))
      (node (ref "U3") (pin "10") (pinfunction "+INC_10") (pintype "bidirectional"))
    )
    (net (code "67") (name "Net-(R6-E)") (class "Default")
      (node (ref "R6") (pin "3") (pinfunction "E_3") (pintype "passive"))
      (node (ref "U9") (pin "6") (pinfunction "-INB_6") (pintype "bidirectional"))
      (node (ref "U9") (pin "7") (pinfunction "OUTB_7") (pintype "bidirectional"))
    )
    (net (code "68") (name "Net-(R6-S)") (class "Default")
      (node (ref "C6") (pin "1") (pinfunction "1_1") (pintype "passive"))
      (node (ref "R6") (pin "2") (pinfunction "S_2") (pintype "passive"))
      (node (ref "U3") (pin "12") (pinfunction "+IND_12") (pintype "bidirectional"))
    )
    (net (code "69") (name "Net-(R7-E)") (class "Default")
      (node (ref "R7") (pin "3") (pinfunction "E_3") (pintype "passive"))
      (node (ref "U9") (pin "8") (pinfunction "OUTC_8") (pintype "bidirectional"))
      (node (ref "U9") (pin "9") (pinfunction "-INC_9") (pintype "bidirectional"))
    )
    (net (code "70") (name "Net-(R7-S)") (class "Default")
      (node (ref "C7") (pin "1") (pinfunction "1_1") (pintype "passive"))
      (node (ref "R7") (pin "2") (pinfunction "S_2") (pintype "passive"))
      (node (ref "U9") (pin "12") (pinfunction "+IND_12") (pintype "bidirectional"))
    )
    (net (code "71") (name "Net-(R14-S)") (class "Default")
      (node (ref "R14") (pin "2") (pinfunction "S_2") (pintype "passive"))
      (node (ref "R17") (pin "2") (pinfunction "2_2") (pintype "passive"))
      (node (ref "U9") (pin "3") (pinfunction "+INA_3") (pintype "bidirectional"))
    )
    (net (code "72") (name "Net-(R15-S)") (class "Default")
      (node (ref "R15") (pin "2") (pinfunction "S_2") (pintype "passive"))
      (node (ref "R18") (pin "2") (pinfunction "2_2") (pintype "passive"))
      (node (ref "U9") (pin "5") (pinfunction "+INB_5") (pintype "bidirectional"))
    )
    (net (code "73") (name "Net-(R16-S)") (class "Default")
      (node (ref "R16") (pin "2") (pinfunction "S_2") (pintype "passive"))
      (node (ref "R19") (pin "2") (pinfunction "2_2") (pintype "passive"))
      (node (ref "U9") (pin "10") (pinfunction "+INC_10") (pintype "bidirectional"))
    )
    (net (code "74") (name "Net-(U1-SOSCI{slash}RP4{slash}CN1{slash}RB4)") (class "Default")
      (node (ref "R2") (pin "2") (pinfunction "2_2") (pintype "passive"))
      (node (ref "U1") (pin "33") (pinfunction "SOSCI/RP4/CN1/RB4_33") (pintype "bidirectional"))
    )
    (net (code "75") (name "Net-(U1-SOSCO{slash}T1CK{slash}CN0{slash}RA4)") (class "Default")
      (node (ref "R3") (pin "2") (pinfunction "2_2") (pintype "passive"))
      (node (ref "U1") (pin "34") (pinfunction "SOSCO/T1CK/CN0/RA4_34") (pintype "bidirectional"))
    )
    (net (code "76") (name "Net-(U1-TDI{slash}PMA9{slash}RA9)") (class "Default")
      (node (ref "R4") (pin "2") (pinfunction "2_2") (pintype "passive"))
      (node (ref "U1") (pin "35") (pinfunction "TDI/PMA9/RA9_35") (pintype "bidirectional"))
    )
    (net (code "77") (name "Net-(U1-TDO{slash}PMA8{slash}RA8)") (class "Default")
      (node (ref "R8") (pin "1") (pinfunction "1_1") (pintype "passive"))
      (node (ref "U1") (pin "32") (pinfunction "TDO/PMA8/RA8_32") (pintype "bidirectional"))
    )
    (net (code "78") (name "Net-(U1-V_CAP)") (class "Default")
      (node (ref "C4") (pin "1") (pinfunction "1_1") (pintype "passive"))
      (node (ref "U1") (pin "7") (pinfunction "V_CAP_7") (pintype "power_in"))
    )
    (net (code "79") (name "Net-(U6-BST)") (class "Default")
      (node (ref "C10") (pin "2") (pinfunction "2_2") (pintype "passive"))
      (node (ref "U6") (pin "10") (pinfunction "BST_10") (pintype "bidirectional"))
    )
    (net (code "80") (name "Net-(U6-CS)") (class "Default")
      (node (ref "D1") (pin "A") (pinfunction "A_A") (pintype "passive"))
      (node (ref "R11") (pin "2") (pinfunction "2_2") (pintype "passive"))
      (node (ref "U6") (pin "8") (pinfunction "CS_8") (pintype "bidirectional"))
    )
    (net (code "81") (name "Net-(U6-CSG)") (class "Default")
      (node (ref "R11") (pin "1") (pinfunction "1_1") (pintype "passive"))
      (node (ref "U6") (pin "7") (pinfunction "CSG_7") (pintype "bidirectional"))
    )
    (net (code "82") (name "Net-(U6-FB)") (class "Default")
      (node (ref "R10") (pin "2") (pinfunction "2_2") (pintype "passive"))
      (node (ref "R9") (pin "1") (pinfunction "1_1") (pintype "passive"))
      (node (ref "U6") (pin "6") (pinfunction "FB_6") (pintype "bidirectional"))
    )
    (net (code "83") (name "Net-(U6-RT)") (class "Default")
      (node (ref "R12") (pin "1") (pinfunction "1_1") (pintype "passive"))
      (node (ref "U6") (pin "2") (pinfunction "RT_2") (pintype "bidirectional"))
    )
    (net (code "84") (name "Net-(U6-SS)") (class "Default")
      (node (ref "C15") (pin "1") (pinfunction "1_1") (pintype "passive"))
      (node (ref "U6") (pin "4") (pinfunction "SS_4") (pintype "bidirectional"))
    )
    (net (code "85") (name "Net-(U6-VIN)") (class "Default")
      (node (ref "C8") (pin "1") (pinfunction "1_1") (pintype "passive"))
      (node (ref "C9") (pin "2") (pinfunction "2_2") (pintype "passive"))
      (node (ref "R12") (pin "2") (pinfunction "2_2") (pintype "passive"))
      (node (ref "U6") (pin "1") (pinfunction "VIN_1") (pintype "bidirectional"))
      (node (ref "X2") (pin "2") (pinfunction "KL_2") (pintype "passive"))
      (node (ref "X3") (pin "1") (pinfunction "KL_1") (pintype "passive"))
    )
    (net (code "86") (name "Net-(X3B-KL)") (class "Default")
      (node (ref "X3") (pin "2") (pinfunction "KL_2") (pintype "passive"))
      (node (ref "X4") (pin "1") (pinfunction "KL_1") (pintype "passive"))
    )
    (net (code "87") (name "unconnected-(SV2-Pad1)") (class "Default")
      (node (ref "SV2") (pin "1") (pinfunction "1_1") (pintype "passive"))
    )
    (net (code "88") (name "unconnected-(SV2-Pad3)") (class "Default")
      (node (ref "SV2") (pin "3") (pinfunction "3_3") (pintype "passive"))
    )
    (net (code "89") (name "unconnected-(SV2-Pad4)") (class "Default")
      (node (ref "SV2") (pin "4") (pinfunction "4_4") (pintype "passive"))
    )
    (net (code "90") (name "unconnected-(SV2-Pad5)") (class "Default")
      (node (ref "SV2") (pin "5") (pinfunction "5_5") (pintype "passive"))
    )
    (net (code "91") (name "unconnected-(SV2-Pad7)") (class "Default")
      (node (ref "SV2") (pin "7") (pinfunction "7_7") (pintype "passive"))
    )
    (net (code "92") (name "unconnected-(SV2-Pad8)") (class "Default")
      (node (ref "SV2") (pin "8") (pinfunction "8_8") (pintype "passive"))
    )
    (net (code "93") (name "unconnected-(SV2-Pad10)") (class "Default")
      (node (ref "SV2") (pin "10") (pinfunction "10_10") (pintype "passive"))
    )
    (net (code "94") (name "unconnected-(SV2-Pad11)") (class "Default")
      (node (ref "SV2") (pin "11") (pinfunction "11_11") (pintype "passive"))
    )
    (net (code "95") (name "unconnected-(SV2-Pad12)") (class "Default")
      (node (ref "SV2") (pin "12") (pinfunction "12_12") (pintype "passive"))
    )
    (net (code "96") (name "unconnected-(SV2-Pad13)") (class "Default")
      (node (ref "SV2") (pin "13") (pinfunction "13_13") (pintype "passive"))
    )
    (net (code "97") (name "unconnected-(SV2-Pad15)") (class "Default")
      (node (ref "SV2") (pin "15") (pinfunction "15_15") (pintype "passive"))
    )
    (net (code "98") (name "unconnected-(SV2-Pad16)") (class "Default")
      (node (ref "SV2") (pin "16") (pinfunction "16_16") (pintype "passive"))
    )
    (net (code "99") (name "unconnected-(SV2-Pad17)") (class "Default")
      (node (ref "SV2") (pin "17") (pinfunction "17_17") (pintype "passive"))
    )
    (net (code "100") (name "unconnected-(SV2-Pad18)") (class "Default")
      (node (ref "SV2") (pin "18") (pinfunction "18_18") (pintype "passive"))
    )
    (net (code "101") (name "unconnected-(SV2-Pad22)") (class "Default")
      (node (ref "SV2") (pin "22") (pinfunction "22_22") (pintype "passive"))
    )
    (net (code "102") (name "unconnected-(SV2-Pad24)") (class "Default")
      (node (ref "SV2") (pin "24") (pinfunction "24_24") (pintype "passive"))
    )
    (net (code "103") (name "unconnected-(SV2-Pad26)") (class "Default")
      (node (ref "SV2") (pin "26") (pinfunction "26_26") (pintype "passive"))
    )
    (net (code "104") (name "unconnected-(SV2-Pad27)") (class "Default")
      (node (ref "SV2") (pin "27") (pinfunction "27_27") (pintype "passive"))
    )
    (net (code "105") (name "unconnected-(SV2-Pad28)") (class "Default")
      (node (ref "SV2") (pin "28") (pinfunction "28_28") (pintype "passive"))
    )
    (net (code "106") (name "unconnected-(SV2-Pad29)") (class "Default")
      (node (ref "SV2") (pin "29") (pinfunction "29_29") (pintype "passive"))
    )
    (net (code "107") (name "unconnected-(SV2-Pad31)") (class "Default")
      (node (ref "SV2") (pin "31") (pinfunction "31_31") (pintype "passive"))
    )
    (net (code "108") (name "unconnected-(SV2-Pad32)") (class "Default")
      (node (ref "SV2") (pin "32") (pinfunction "32_32") (pintype "passive"))
    )
    (net (code "109") (name "unconnected-(SV2-Pad33)") (class "Default")
      (node (ref "SV2") (pin "33") (pinfunction "33_33") (pintype "passive"))
    )
    (net (code "110") (name "unconnected-(SV2-Pad35)") (class "Default")
      (node (ref "SV2") (pin "35") (pinfunction "35_35") (pintype "passive"))
    )
    (net (code "111") (name "unconnected-(SV2-Pad36)") (class "Default")
      (node (ref "SV2") (pin "36") (pinfunction "36_36") (pintype "passive"))
    )
    (net (code "112") (name "unconnected-(SV2-Pad37)") (class "Default")
      (node (ref "SV2") (pin "37") (pinfunction "37_37") (pintype "passive"))
    )
    (net (code "113") (name "unconnected-(SV2-Pad38)") (class "Default")
      (node (ref "SV2") (pin "38") (pinfunction "38_38") (pintype "passive"))
    )
    (net (code "114") (name "unconnected-(SV2-Pad40)") (class "Default")
      (node (ref "SV2") (pin "40") (pinfunction "40_40") (pintype "passive"))
    )
    (net (code "115") (name "unconnected-(U6-PGD-Pad3)") (class "Default")
      (node (ref "U6") (pin "3") (pinfunction "PGD_3") (pintype "bidirectional"))
    )
  )
)
